# Teletupsud-Schematic.net
KiCad netlist of a schematic drawn in Altium Designer
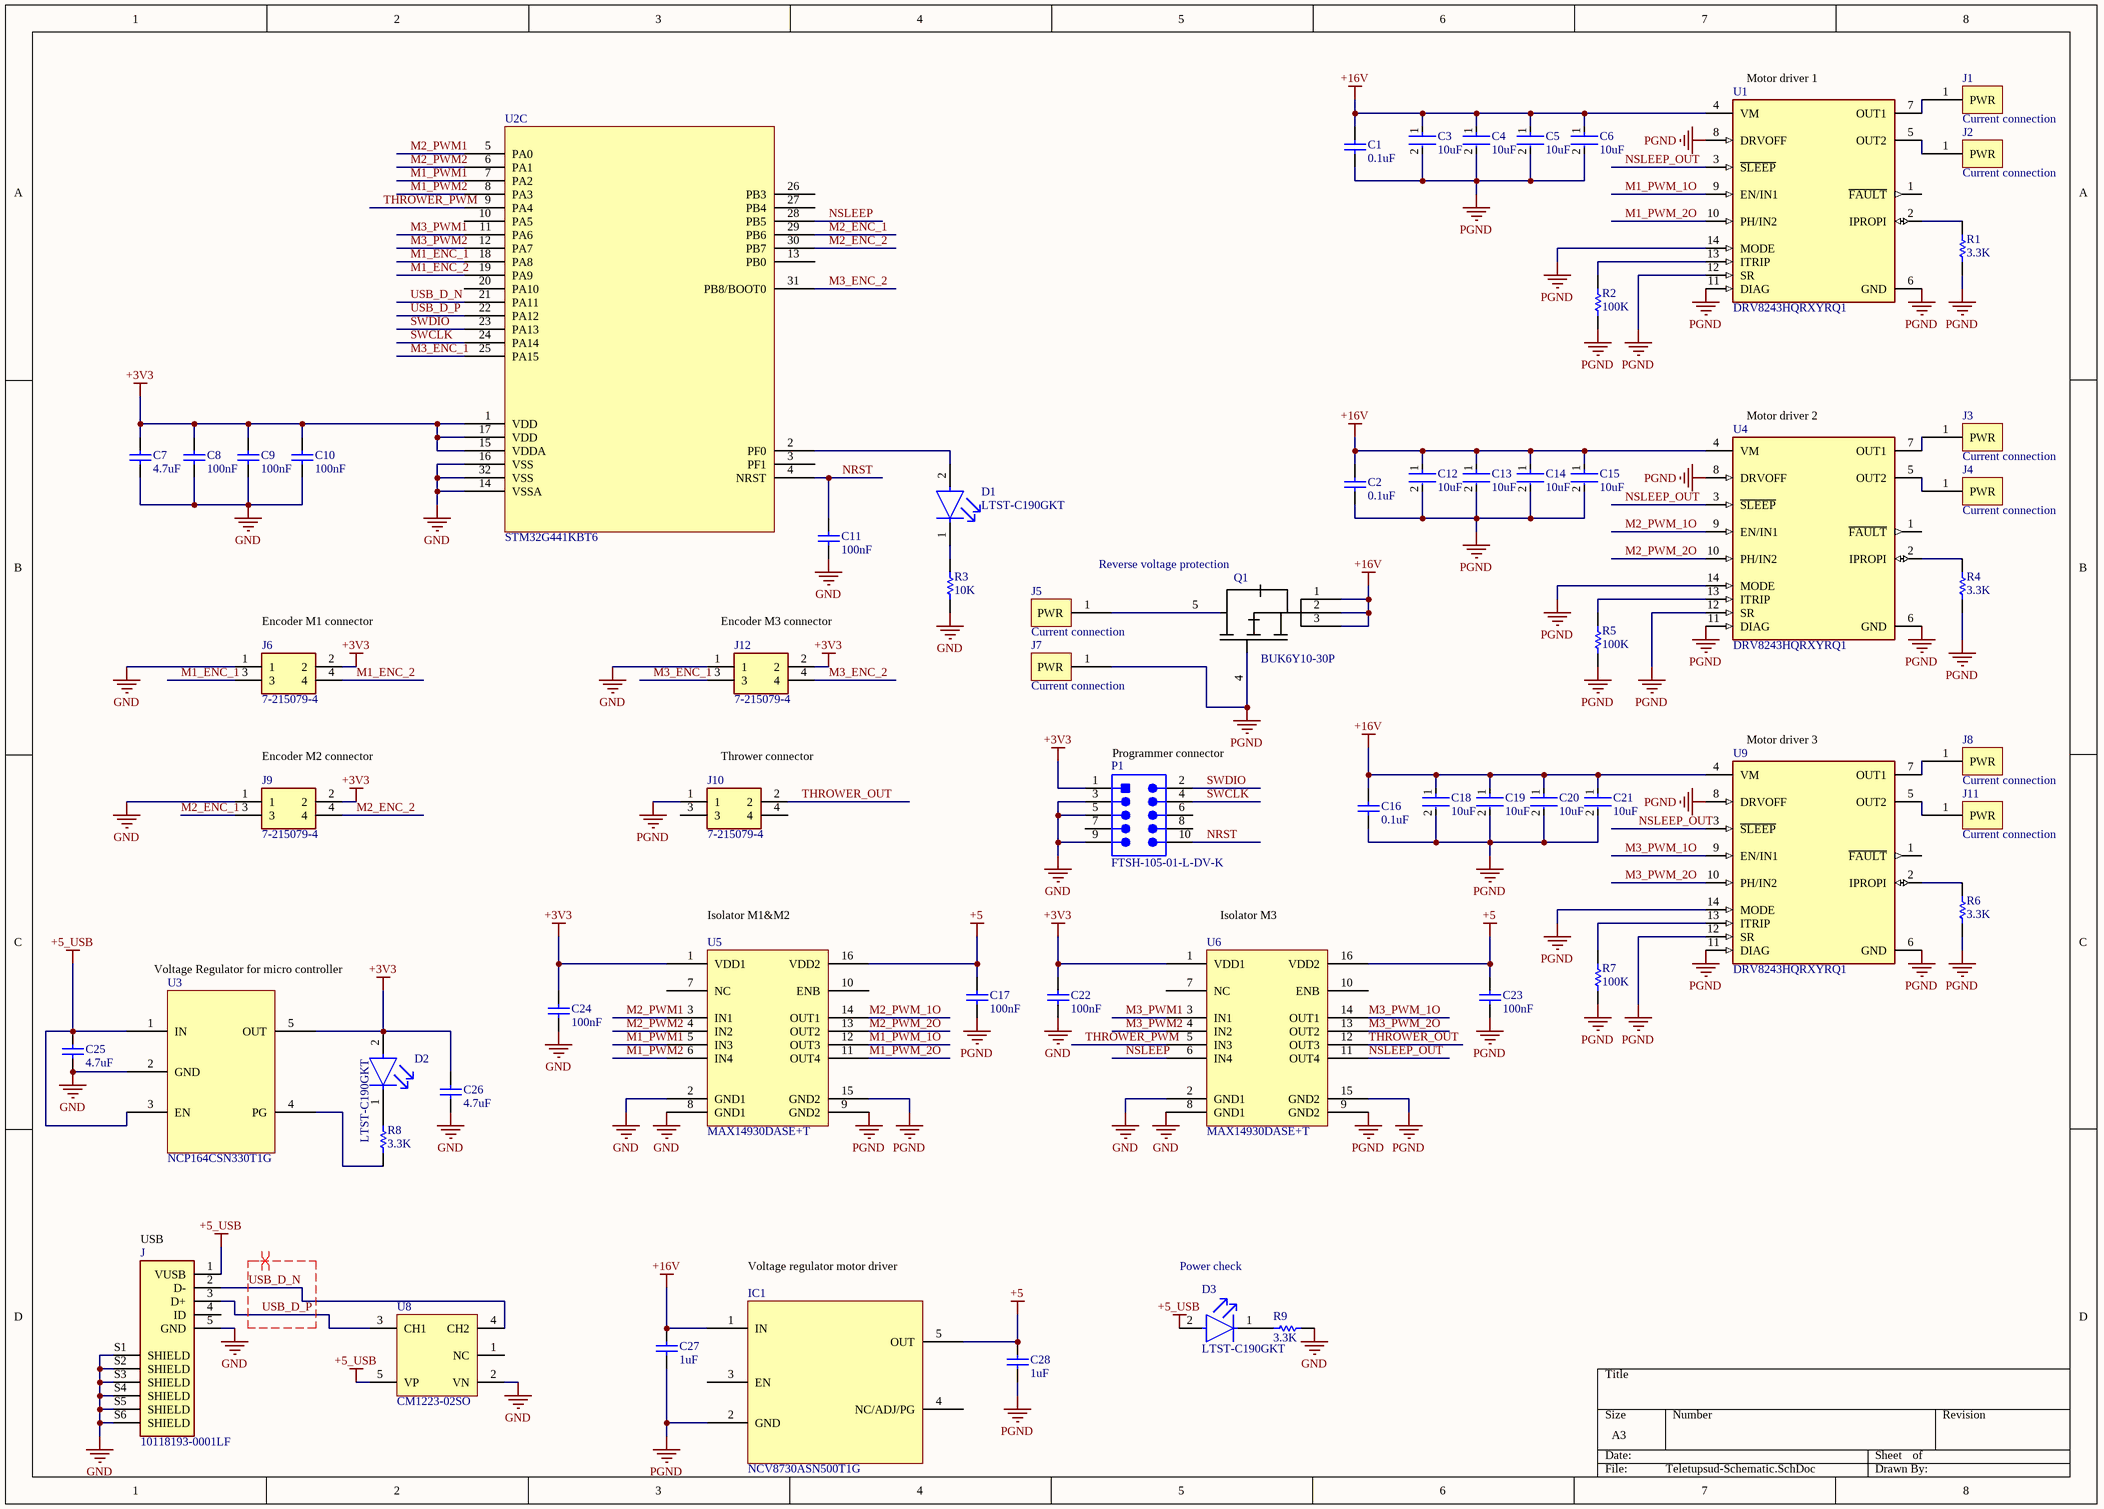
[diagram p0: Teletupsud-Schematic.SchDoc]

(export (version "E")
  (design (tool "Eeschema 10.0.6"))
  (components
    (comp (ref "C1")
      (value "0.1uF")
      (footprint "CAPC1608X90X35ML10T15")
      (description "Chip Capacitor, 22 pF, +/- 5%, 50 V, -55 to 125 degC, 0603 (1608 Metric), RoHS, Tape and Reel")
      (fields (field (name "MANUFACTURER") "Murata"))
      (libsource (lib "Altium Content Vault") (part "CAP-NP-2"))
    )
    (comp (ref "C2")
      (value "0.1uF")
      (footprint "CAPC1608X90X35ML10T15")
      (description "Chip Capacitor, 22 pF, +/- 5%, 50 V, -55 to 125 degC, 0603 (1608 Metric), RoHS, Tape and Reel")
      (fields (field (name "MANUFACTURER") "Murata"))
      (libsource (lib "Altium Content Vault") (part "CAP-NP-2"))
    )
    (comp (ref "C3")
      (value "10uF")
      (footprint "FP-GRM21B-0_15-IPC_A")
      (description "CAP CER 10UF 25V X5R 0805")
      (fields (field (name "VOLTAGE") "25V") (field (name "TOLERANCE") "10%"))
      (libsource (lib "Teletupsud") (part "b4654b650e69147ec39a6b967a45e02"))
    )
    (comp (ref "C4")
      (value "10uF")
      (footprint "FP-GRM21B-0_15-IPC_A")
      (description "CAP CER 10UF 25V X5R 0805")
      (fields (field (name "VOLTAGE") "25V") (field (name "TOLERANCE") "10%"))
      (libsource (lib "Teletupsud") (part "b4654b650e69147ec39a6b967a45e02"))
    )
    (comp (ref "C5")
      (value "10uF")
      (footprint "FP-GRM21B-0_15-IPC_A")
      (description "CAP CER 10UF 25V X5R 0805")
      (fields (field (name "VOLTAGE") "25V") (field (name "TOLERANCE") "10%"))
      (libsource (lib "Teletupsud") (part "b4654b650e69147ec39a6b967a45e02"))
    )
    (comp (ref "C6")
      (value "10uF")
      (footprint "FP-GRM21B-0_15-IPC_A")
      (description "CAP CER 10UF 25V X5R 0805")
      (fields (field (name "VOLTAGE") "25V") (field (name "TOLERANCE") "10%"))
      (libsource (lib "Teletupsud") (part "b4654b650e69147ec39a6b967a45e02"))
    )
    (comp (ref "C7")
      (value "4.7uF")
      (footprint "CAPC1608X90X35ML10T15")
      (description "Chip Capacitor, 22 pF, +/- 5%, 50 V, -55 to 125 degC, 0603 (1608 Metric), RoHS, Tape and Reel")
      (fields (field (name "MANUFACTURER") "Murata"))
      (libsource (lib "Altium Content Vault") (part "CAP-NP-2"))
    )
    (comp (ref "C8")
      (value "100nF")
      (footprint "CAPC1608X90X35ML10T15")
      (description "Chip Capacitor, 22 pF, +/- 5%, 50 V, -55 to 125 degC, 0603 (1608 Metric), RoHS, Tape and Reel")
      (fields (field (name "MANUFACTURER") "Murata"))
      (libsource (lib "Altium Content Vault") (part "CAP-NP-2"))
    )
    (comp (ref "C9")
      (value "100nF")
      (footprint "CAPC1608X90X35ML10T15")
      (description "Chip Capacitor, 22 pF, +/- 5%, 50 V, -55 to 125 degC, 0603 (1608 Metric), RoHS, Tape and Reel")
      (fields (field (name "MANUFACTURER") "Murata"))
      (libsource (lib "Altium Content Vault") (part "CAP-NP-2"))
    )
    (comp (ref "C10")
      (value "100nF")
      (footprint "CAPC1608X90X35ML10T15")
      (description "Chip Capacitor, 22 pF, +/- 5%, 50 V, -55 to 125 degC, 0603 (1608 Metric), RoHS, Tape and Reel")
      (fields (field (name "MANUFACTURER") "Murata"))
      (libsource (lib "Altium Content Vault") (part "CAP-NP-2"))
    )
    (comp (ref "C11")
      (value "100nF")
      (footprint "CAPC1608X90X35ML10T15")
      (description "Chip Capacitor, 22 pF, +/- 5%, 50 V, -55 to 125 degC, 0603 (1608 Metric), RoHS, Tape and Reel")
      (fields (field (name "MANUFACTURER") "Murata"))
      (libsource (lib "Altium Content Vault") (part "CAP-NP-2"))
    )
    (comp (ref "C12")
      (value "10uF")
      (footprint "FP-GRM21B-0_15-IPC_A")
      (description "CAP CER 10UF 25V X5R 0805")
      (fields (field (name "VOLTAGE") "25V") (field (name "TOLERANCE") "10%"))
      (libsource (lib "Teletupsud") (part "b4654b650e69147ec39a6b967a45e02"))
    )
    (comp (ref "C13")
      (value "10uF")
      (footprint "FP-GRM21B-0_15-IPC_A")
      (description "CAP CER 10UF 25V X5R 0805")
      (fields (field (name "VOLTAGE") "25V") (field (name "TOLERANCE") "10%"))
      (libsource (lib "Teletupsud") (part "b4654b650e69147ec39a6b967a45e02"))
    )
    (comp (ref "C14")
      (value "10uF")
      (footprint "FP-GRM21B-0_15-IPC_A")
      (description "CAP CER 10UF 25V X5R 0805")
      (fields (field (name "VOLTAGE") "25V") (field (name "TOLERANCE") "10%"))
      (libsource (lib "Teletupsud") (part "b4654b650e69147ec39a6b967a45e02"))
    )
    (comp (ref "C15")
      (value "10uF")
      (footprint "FP-GRM21B-0_15-IPC_A")
      (description "CAP CER 10UF 25V X5R 0805")
      (fields (field (name "VOLTAGE") "25V") (field (name "TOLERANCE") "10%"))
      (libsource (lib "Teletupsud") (part "b4654b650e69147ec39a6b967a45e02"))
    )
    (comp (ref "C16")
      (value "0.1uF")
      (footprint "CAPC1608X90X35ML10T15")
      (description "Chip Capacitor, 22 pF, +/- 5%, 50 V, -55 to 125 degC, 0603 (1608 Metric), RoHS, Tape and Reel")
      (fields (field (name "MANUFACTURER") "Murata"))
      (libsource (lib "Altium Content Vault") (part "CAP-NP-2"))
    )
    (comp (ref "C17")
      (value "100nF")
      (footprint "CAPC1608X90X35ML10T15")
      (description "Chip Capacitor, 22 pF, +/- 5%, 50 V, -55 to 125 degC, 0603 (1608 Metric), RoHS, Tape and Reel")
      (fields (field (name "MANUFACTURER") "Murata"))
      (libsource (lib "Altium Content Vault") (part "CAP-NP-2"))
    )
    (comp (ref "C18")
      (value "10uF")
      (footprint "FP-GRM21B-0_15-IPC_A")
      (description "CAP CER 10UF 25V X5R 0805")
      (fields (field (name "VOLTAGE") "25V") (field (name "TOLERANCE") "10%"))
      (libsource (lib "Teletupsud") (part "b4654b650e69147ec39a6b967a45e02"))
    )
    (comp (ref "C19")
      (value "10uF")
      (footprint "FP-GRM21B-0_15-IPC_A")
      (description "CAP CER 10UF 25V X5R 0805")
      (fields (field (name "VOLTAGE") "25V") (field (name "TOLERANCE") "10%"))
      (libsource (lib "Teletupsud") (part "b4654b650e69147ec39a6b967a45e02"))
    )
    (comp (ref "C20")
      (value "10uF")
      (footprint "FP-GRM21B-0_15-IPC_A")
      (description "CAP CER 10UF 25V X5R 0805")
      (fields (field (name "VOLTAGE") "25V") (field (name "TOLERANCE") "10%"))
      (libsource (lib "Teletupsud") (part "b4654b650e69147ec39a6b967a45e02"))
    )
    (comp (ref "C21")
      (value "10uF")
      (footprint "FP-GRM21B-0_15-IPC_A")
      (description "CAP CER 10UF 25V X5R 0805")
      (fields (field (name "VOLTAGE") "25V") (field (name "TOLERANCE") "10%"))
      (libsource (lib "Teletupsud") (part "b4654b650e69147ec39a6b967a45e02"))
    )
    (comp (ref "C22")
      (value "100nF")
      (footprint "CAPC1608X90X35ML10T15")
      (description "Chip Capacitor, 22 pF, +/- 5%, 50 V, -55 to 125 degC, 0603 (1608 Metric), RoHS, Tape and Reel")
      (fields (field (name "MANUFACTURER") "Murata"))
      (libsource (lib "Altium Content Vault") (part "CAP-NP-2"))
    )
    (comp (ref "C23")
      (value "100nF")
      (footprint "CAPC1608X90X35ML10T15")
      (description "Chip Capacitor, 22 pF, +/- 5%, 50 V, -55 to 125 degC, 0603 (1608 Metric), RoHS, Tape and Reel")
      (fields (field (name "MANUFACTURER") "Murata"))
      (libsource (lib "Altium Content Vault") (part "CAP-NP-2"))
    )
    (comp (ref "C24")
      (value "100nF")
      (footprint "CAPC1608X90X35ML10T15")
      (description "Chip Capacitor, 22 pF, +/- 5%, 50 V, -55 to 125 degC, 0603 (1608 Metric), RoHS, Tape and Reel")
      (fields (field (name "MANUFACTURER") "Murata"))
      (libsource (lib "Altium Content Vault") (part "CAP-NP-2"))
    )
    (comp (ref "C25")
      (value "4.7uF")
      (footprint "CAPC1608X90X35ML10T15")
      (description "Chip Capacitor, 22 pF, +/- 5%, 50 V, -55 to 125 degC, 0603 (1608 Metric), RoHS, Tape and Reel")
      (fields (field (name "MANUFACTURER") "Murata"))
      (libsource (lib "Altium Content Vault") (part "CAP-NP-2"))
    )
    (comp (ref "C26")
      (value "4.7uF")
      (footprint "CAPC1608X90X35ML10T15")
      (description "Chip Capacitor, 22 pF, +/- 5%, 50 V, -55 to 125 degC, 0603 (1608 Metric), RoHS, Tape and Reel")
      (fields (field (name "MANUFACTURER") "Murata"))
      (libsource (lib "Altium Content Vault") (part "CAP-NP-2"))
    )
    (comp (ref "C27")
      (value "1uF")
      (footprint "CAPC1608X90X35ML10T15")
      (description "Chip Capacitor, 22 pF, +/- 5%, 50 V, -55 to 125 degC, 0603 (1608 Metric), RoHS, Tape and Reel")
      (fields (field (name "MANUFACTURER") "Murata"))
      (libsource (lib "Altium Content Vault") (part "CAP-NP-2"))
    )
    (comp (ref "C28")
      (value "1uF")
      (footprint "CAPC1608X90X35ML10T15")
      (description "Chip Capacitor, 22 pF, +/- 5%, 50 V, -55 to 125 degC, 0603 (1608 Metric), RoHS, Tape and Reel")
      (fields (field (name "MANUFACTURER") "Murata"))
      (libsource (lib "Altium Content Vault") (part "CAP-NP-2"))
    )
    (comp (ref "D1")
      (value "LTST-C190GKT")
      (footprint "FP-LTST-C190GKT-MFG")
      (description "LED Uni-Color Green 565nm 2-Pin Chip LED T/R")
      (fields (field (name "VOLTAGE") "2V"))
      (libsource (lib "Teletupsud") (part "8706943c75ba83719d021d2fdc84c58"))
    )
    (comp (ref "D2")
      (value "LTST-C190GKT")
      (footprint "FP-LTST-C190GKT-MFG")
      (description "LED Uni-Color Green 565nm 2-Pin Chip LED T/R")
      (fields (field (name "VOLTAGE") "2V"))
      (libsource (lib "Teletupsud") (part "8706943c75ba83719d021d2fdc84c58"))
    )
    (comp (ref "D3")
      (value "LTST-C190GKT")
      (footprint "FP-LTST-C190GKT-MFG")
      (description "LED GREEN CLEAR CHIP SMD")
      (fields (field (name "VOLTAGE") "2V"))
      (libsource (lib "Altium Content Vault") (part "8706943c75ba83719d021d2fdc84c58"))
    )
    (comp (ref "IC1")
      (value "NCV8730ASN500T1G")
      (footprint "SOP95P275X110-5N")
      (libsource (lib "") (part "New symbol 1_3"))
    )
    (comp (ref "J")
      (value "10118193-0001LF")
      (footprint "FCI_10118193-0001LF")
      (description "USB - micro B USB 2.0 Receptacle Connector 5 Position Surface Mount, Right Angle; Through Hole")
      (fields (field (name "MF") "Amphenol ICC"))
      (libsource (lib "Teletupsud") (part "10118193-0001LF"))
    )
    (comp (ref "J1")
      (value "Current connection")
      (footprint "New footprint 1")
      (libsource (lib "Teletupsud") (part "New symbol 1"))
    )
    (comp (ref "J2")
      (value "Current connection")
      (footprint "New footprint 1")
      (libsource (lib "Teletupsud") (part "New symbol 1"))
    )
    (comp (ref "J3")
      (value "Current connection")
      (footprint "New footprint 1")
      (libsource (lib "Teletupsud") (part "New symbol 1"))
    )
    (comp (ref "J4")
      (value "Current connection")
      (footprint "New footprint 1")
      (libsource (lib "Teletupsud") (part "New symbol 1"))
    )
    (comp (ref "J5")
      (value "Current connection")
      (footprint "New footprint 1")
      (libsource (lib "") (part "New symbol 1_2"))
    )
    (comp (ref "J6")
      (value "7-215079-4")
      (footprint "TE_7-215079-4")
      (description "Micro-MaTch 4 Position 1.27 mm Pitch Vertical Female-on-Board Connector")
      (fields (field (name "MF") "TE Connectivity"))
      (libsource (lib "Teletupsud") (part "7-215079-4"))
    )
    (comp (ref "J7")
      (value "Current connection")
      (footprint "New footprint 1")
      (libsource (lib "") (part "New symbol 1_2"))
    )
    (comp (ref "J8")
      (value "Current connection")
      (footprint "New footprint 1")
      (libsource (lib "Teletupsud") (part "New symbol 1"))
    )
    (comp (ref "J9")
      (value "7-215079-4")
      (footprint "TE_7-215079-4")
      (description "Micro-MaTch 4 Position 1.27 mm Pitch Vertical Female-on-Board Connector")
      (fields (field (name "MF") "TE Connectivity"))
      (libsource (lib "Teletupsud") (part "7-215079-4"))
    )
    (comp (ref "J10")
      (value "7-215079-4")
      (footprint "TE_7-215079-4")
      (description "Micro-MaTch 4 Position 1.27 mm Pitch Vertical Female-on-Board Connector")
      (fields (field (name "MF") "TE Connectivity"))
      (libsource (lib "Teletupsud") (part "7-215079-4"))
    )
    (comp (ref "J11")
      (value "Current connection")
      (footprint "New footprint 1")
      (libsource (lib "Teletupsud") (part "New symbol 1"))
    )
    (comp (ref "J12")
      (value "7-215079-4")
      (footprint "TE_7-215079-4")
      (description "Micro-MaTch 4 Position 1.27 mm Pitch Vertical Female-on-Board Connector")
      (fields (field (name "MF") "TE Connectivity"))
      (libsource (lib "Teletupsud") (part "7-215079-4"))
    )
    (comp (ref "P1")
      (value "FTSH-105-01-L-DV-K")
      (footprint "SMTC-FTSH-105-01-L-DV-K_V")
      (description "Male Header, Pitch 1.27 mm, 2 x 5 Position, Height 6.25 mm")
      (fields (field (name "MANUFACTURER") "Samtec"))
      (libsource (lib "Altium Content Vault") (part "CN-2P-M-R10"))
    )
    (comp (ref "Q1")
      (value "BUK6Y10-30P")
      (footprint "TO127P600X120-5N")
      (libsource (lib "") (part "New symbol 1_1"))
    )
    (comp (ref "R1")
      (value "3.3K")
      (footprint "RESC1609X50X30NL8T20")
      (description "Chip Resistor, 0 Ohm, Jumper, 100 mW, -55 to 155 degC, 0603 (1608 Metric), RoHS, Tape and Reel")
      (fields (field (name "MANUFACTURER") "Vishay Semiconductor"))
      (libsource (lib "Altium Content Vault") (part "RES-2"))
    )
    (comp (ref "R2")
      (value "100K")
      (footprint "RESC1609X50X30NL8T20")
      (description "Chip Resistor, 0 Ohm, Jumper, 100 mW, -55 to 155 degC, 0603 (1608 Metric), RoHS, Tape and Reel")
      (fields (field (name "MANUFACTURER") "Vishay Semiconductor"))
      (libsource (lib "Altium Content Vault") (part "RES-2"))
    )
    (comp (ref "R3")
      (value "10K")
      (footprint "RESC1609X50X30NL8T20")
      (description "Chip Resistor, 0 Ohm, Jumper, 100 mW, -55 to 155 degC, 0603 (1608 Metric), RoHS, Tape and Reel")
      (fields (field (name "MANUFACTURER") "Vishay Semiconductor"))
      (libsource (lib "Altium Content Vault") (part "RES-2"))
    )
    (comp (ref "R4")
      (value "3.3K")
      (footprint "RESC1609X50X30NL8T20")
      (description "Chip Resistor, 0 Ohm, Jumper, 100 mW, -55 to 155 degC, 0603 (1608 Metric), RoHS, Tape and Reel")
      (fields (field (name "MANUFACTURER") "Vishay Semiconductor"))
      (libsource (lib "Altium Content Vault") (part "RES-2"))
    )
    (comp (ref "R5")
      (value "100K")
      (footprint "RESC1609X50X30NL8T20")
      (description "Chip Resistor, 0 Ohm, Jumper, 100 mW, -55 to 155 degC, 0603 (1608 Metric), RoHS, Tape and Reel")
      (fields (field (name "MANUFACTURER") "Vishay Semiconductor"))
      (libsource (lib "Altium Content Vault") (part "RES-2"))
    )
    (comp (ref "R6")
      (value "3.3K")
      (footprint "RESC1609X50X30NL8T20")
      (description "Chip Resistor, 0 Ohm, Jumper, 100 mW, -55 to 155 degC, 0603 (1608 Metric), RoHS, Tape and Reel")
      (fields (field (name "MANUFACTURER") "Vishay Semiconductor"))
      (libsource (lib "Altium Content Vault") (part "RES-2"))
    )
    (comp (ref "R7")
      (value "100K")
      (footprint "RESC1609X50X30NL8T20")
      (description "Chip Resistor, 0 Ohm, Jumper, 100 mW, -55 to 155 degC, 0603 (1608 Metric), RoHS, Tape and Reel")
      (fields (field (name "MANUFACTURER") "Vishay Semiconductor"))
      (libsource (lib "Altium Content Vault") (part "RES-2"))
    )
    (comp (ref "R8")
      (value "3.3K")
      (footprint "RESC1609X50X30NL8T20")
      (description "Chip Resistor, 0 Ohm, Jumper, 100 mW, -55 to 155 degC, 0603 (1608 Metric), RoHS, Tape and Reel")
      (fields (field (name "MANUFACTURER") "Vishay Semiconductor"))
      (libsource (lib "Altium Content Vault") (part "RES-2"))
    )
    (comp (ref "R9")
      (value "3.3K")
      (footprint "RESC1609X50X30NL8T20")
      (description "Chip Resistor, 0 Ohm, Jumper, 100 mW, -55 to 155 degC, 0603 (1608 Metric), RoHS, Tape and Reel")
      (fields (field (name "MANUFACTURER") "Vishay Semiconductor"))
      (libsource (lib "Altium Content Vault") (part "RES-2"))
    )
    (comp (ref "U1")
      (value "DRV8243HQRXYRQ1")
      (footprint "FP-RXY0014A-MFG")
      (libsource (lib "Teletupsud") (part "e63e13eb07ecfdbca845f52d5221c39"))
    )
    (comp (ref "U2")
      (value "STM32G441KBT6")
      (footprint "QFP32_STM32")
      (libsource (lib "Teletupsud") (part "STM32G441KBT6"))
    )
    (comp (ref "U3")
      (value "NCP164CSN330T1G")
      (footprint "SOP95P275X110-5N")
      (libsource (lib "Teletupsud") (part "NCP164CSN330T1G-Symbol-1"))
    )
    (comp (ref "U4")
      (value "DRV8243HQRXYRQ1")
      (footprint "FP-RXY0014A-MFG")
      (libsource (lib "Teletupsud") (part "e63e13eb07ecfdbca845f52d5221c39"))
    )
    (comp (ref "U5")
      (value "MAX14930DASE+T")
      (footprint "SOIC127P600X175-16N")
      (description "Digital Isolator, 4Ch, -40 To 125Deg C Rohs Compliant: Yes")
      (libsource (lib "Teletupsud") (part "MAX14930DASE+T-Symbol-1"))
    )
    (comp (ref "U6")
      (value "MAX14930DASE+T")
      (footprint "SOIC127P600X175-16N")
      (description "Digital Isolator, 4Ch, -40 To 125Deg C Rohs Compliant: Yes")
      (libsource (lib "Teletupsud") (part "MAX14930DASE+T-Symbol-1"))
    )
    (comp (ref "U8")
      (value "CM1223-02SO")
      (footprint "ONSC-SOT23-5-527AH-01_L")
      (fields (field (name "MANUFACTURER") "On Semiconductor"))
      (libsource (lib "Altium Content Vault") (part "ONSC-CM1223-SOT-23-5-527AH-01"))
    )
    (comp (ref "U9")
      (value "DRV8243HQRXYRQ1")
      (footprint "FP-RXY0014A-MFG")
      (libsource (lib "Teletupsud") (part "e63e13eb07ecfdbca845f52d5221c39"))
    )
  )
  (nets
    (net (code "1") (name "+3V3") (class "Default")
      (node (ref "C10") (pin "2") (pinfunction "2_2") (pintype "passive"))
      (node (ref "C22") (pin "2") (pinfunction "2_2") (pintype "passive"))
      (node (ref "C24") (pin "2") (pinfunction "2_2") (pintype "passive"))
      (node (ref "C26") (pin "2") (pinfunction "2_2") (pintype "passive"))
      (node (ref "C7") (pin "2") (pinfunction "2_2") (pintype "passive"))
      (node (ref "C8") (pin "2") (pinfunction "2_2") (pintype "passive"))
      (node (ref "C9") (pin "2") (pinfunction "2_2") (pintype "passive"))
      (node (ref "D2") (pin "2") (pinfunction "A_2") (pintype "passive"))
      (node (ref "J12") (pin "2") (pinfunction "2_2") (pintype "passive"))
      (node (ref "J6") (pin "2") (pinfunction "2_2") (pintype "passive"))
      (node (ref "J9") (pin "2") (pinfunction "2_2") (pintype "passive"))
      (node (ref "P1") (pin "1") (pinfunction "1_1") (pintype "passive"))
      (node (ref "U2") (pin "1") (pinfunction "VDD_1") (pintype "passive"))
      (node (ref "U2") (pin "15") (pinfunction "VDDA_15") (pintype "passive"))
      (node (ref "U2") (pin "17") (pinfunction "VDD_17") (pintype "passive"))
      (node (ref "U3") (pin "5") (pinfunction "OUT_5") (pintype "passive"))
      (node (ref "U5") (pin "1") (pinfunction "VDD1_1") (pintype "passive"))
      (node (ref "U6") (pin "1") (pinfunction "VDD1_1") (pintype "passive"))
    )
    (net (code "2") (name "+5") (class "Default")
      (node (ref "C17") (pin "2") (pinfunction "2_2") (pintype "passive"))
      (node (ref "C23") (pin "2") (pinfunction "2_2") (pintype "passive"))
      (node (ref "C28") (pin "2") (pinfunction "2_2") (pintype "passive"))
      (node (ref "IC1") (pin "5") (pinfunction "OUT_5") (pintype "passive"))
      (node (ref "U5") (pin "16") (pinfunction "VDD2_16") (pintype "passive"))
      (node (ref "U6") (pin "16") (pinfunction "VDD2_16") (pintype "passive"))
    )
    (net (code "3") (name "+5_USB") (class "Default")
      (node (ref "C25") (pin "2") (pinfunction "2_2") (pintype "passive"))
      (node (ref "D3") (pin "2") (pinfunction "A_2") (pintype "passive"))
      (node (ref "J") (pin "1") (pinfunction "VUSB_1") (pintype "passive"))
      (node (ref "U3") (pin "1") (pinfunction "IN_1") (pintype "passive"))
      (node (ref "U3") (pin "3") (pinfunction "EN_3") (pintype "passive"))
      (node (ref "U8") (pin "5") (pinfunction "VP_5") (pintype "power_in"))
    )
    (net (code "4") (name "+16V") (class "Default")
      (node (ref "C1") (pin "2") (pinfunction "2_2") (pintype "passive"))
      (node (ref "C12") (pin "1") (pinfunction "1_1") (pintype "passive"))
      (node (ref "C13") (pin "1") (pinfunction "1_1") (pintype "passive"))
      (node (ref "C14") (pin "1") (pinfunction "1_1") (pintype "passive"))
      (node (ref "C15") (pin "1") (pinfunction "1_1") (pintype "passive"))
      (node (ref "C16") (pin "2") (pinfunction "2_2") (pintype "passive"))
      (node (ref "C18") (pin "1") (pinfunction "1_1") (pintype "passive"))
      (node (ref "C19") (pin "1") (pinfunction "1_1") (pintype "passive"))
      (node (ref "C2") (pin "2") (pinfunction "2_2") (pintype "passive"))
      (node (ref "C20") (pin "1") (pinfunction "1_1") (pintype "passive"))
      (node (ref "C21") (pin "1") (pinfunction "1_1") (pintype "passive"))
      (node (ref "C27") (pin "2") (pinfunction "2_2") (pintype "passive"))
      (node (ref "C3") (pin "1") (pinfunction "1_1") (pintype "passive"))
      (node (ref "C4") (pin "1") (pinfunction "1_1") (pintype "passive"))
      (node (ref "C5") (pin "1") (pinfunction "1_1") (pintype "passive"))
      (node (ref "C6") (pin "1") (pinfunction "1_1") (pintype "passive"))
      (node (ref "IC1") (pin "1") (pinfunction "IN_1") (pintype "passive"))
      (node (ref "Q1") (pin "1") (pintype "passive"))
      (node (ref "Q1") (pin "2") (pintype "passive"))
      (node (ref "Q1") (pin "3") (pintype "passive"))
      (node (ref "U1") (pin "4") (pinfunction "VM_4") (pintype "power_in"))
      (node (ref "U4") (pin "4") (pinfunction "VM_4") (pintype "power_in"))
      (node (ref "U9") (pin "4") (pinfunction "VM_4") (pintype "power_in"))
    )
    (net (code "5") (name "/M1_ENC_1") (class "Default")
      (node (ref "J6") (pin "3") (pinfunction "3_3") (pintype "passive"))
      (node (ref "U2") (pin "18") (pinfunction "PA8_18") (pintype "passive"))
    )
    (net (code "6") (name "/M1_ENC_2") (class "Default")
      (node (ref "J6") (pin "4") (pinfunction "4_4") (pintype "passive"))
      (node (ref "U2") (pin "19") (pinfunction "PA9_19") (pintype "passive"))
    )
    (net (code "7") (name "/M1_PWM1") (class "Default")
      (node (ref "U2") (pin "7") (pinfunction "PA2_7") (pintype "passive"))
      (node (ref "U5") (pin "5") (pinfunction "IN3_5") (pintype "passive"))
    )
    (net (code "8") (name "/M1_PWM2") (class "Default")
      (node (ref "U2") (pin "8") (pinfunction "PA3_8") (pintype "passive"))
      (node (ref "U5") (pin "6") (pinfunction "IN4_6") (pintype "passive"))
    )
    (net (code "9") (name "/M1_PWM_1O") (class "Default")
      (node (ref "U1") (pin "9") (pinfunction "EN/IN1_9") (pintype "input"))
      (node (ref "U5") (pin "12") (pinfunction "OUT3_12") (pintype "passive"))
    )
    (net (code "10") (name "/M1_PWM_2O") (class "Default")
      (node (ref "U1") (pin "10") (pinfunction "PH/IN2_10") (pintype "input"))
      (node (ref "U5") (pin "11") (pinfunction "OUT4_11") (pintype "passive"))
    )
    (net (code "11") (name "/M2_ENC_1") (class "Default")
      (node (ref "J9") (pin "3") (pinfunction "3_3") (pintype "passive"))
      (node (ref "U2") (pin "29") (pinfunction "PB6_29") (pintype "passive"))
    )
    (net (code "12") (name "/M2_ENC_2") (class "Default")
      (node (ref "J9") (pin "4") (pinfunction "4_4") (pintype "passive"))
      (node (ref "U2") (pin "30") (pinfunction "PB7_30") (pintype "passive"))
    )
    (net (code "13") (name "/M2_PWM1") (class "Default")
      (node (ref "U2") (pin "5") (pinfunction "PA0_5") (pintype "passive"))
      (node (ref "U5") (pin "3") (pinfunction "IN1_3") (pintype "passive"))
    )
    (net (code "14") (name "/M2_PWM2") (class "Default")
      (node (ref "U2") (pin "6") (pinfunction "PA1_6") (pintype "passive"))
      (node (ref "U5") (pin "4") (pinfunction "IN2_4") (pintype "passive"))
    )
    (net (code "15") (name "/M2_PWM_1O") (class "Default")
      (node (ref "U4") (pin "9") (pinfunction "EN/IN1_9") (pintype "input"))
      (node (ref "U5") (pin "14") (pinfunction "OUT1_14") (pintype "passive"))
    )
    (net (code "16") (name "/M2_PWM_2O") (class "Default")
      (node (ref "U4") (pin "10") (pinfunction "PH/IN2_10") (pintype "input"))
      (node (ref "U5") (pin "13") (pinfunction "OUT2_13") (pintype "passive"))
    )
    (net (code "17") (name "/M3_ENC_1") (class "Default")
      (node (ref "J12") (pin "3") (pinfunction "3_3") (pintype "passive"))
      (node (ref "U2") (pin "25") (pinfunction "PA15_25") (pintype "passive"))
    )
    (net (code "18") (name "/M3_ENC_2") (class "Default")
      (node (ref "J12") (pin "4") (pinfunction "4_4") (pintype "passive"))
      (node (ref "U2") (pin "31") (pinfunction "PB8/BOOT0_31") (pintype "passive"))
    )
    (net (code "19") (name "/M3_PWM1") (class "Default")
      (node (ref "U2") (pin "11") (pinfunction "PA6_11") (pintype "passive"))
      (node (ref "U6") (pin "3") (pinfunction "IN1_3") (pintype "passive"))
    )
    (net (code "20") (name "/M3_PWM2") (class "Default")
      (node (ref "U2") (pin "12") (pinfunction "PA7_12") (pintype "passive"))
      (node (ref "U6") (pin "4") (pinfunction "IN2_4") (pintype "passive"))
    )
    (net (code "21") (name "/M3_PWM_1O") (class "Default")
      (node (ref "U6") (pin "14") (pinfunction "OUT1_14") (pintype "passive"))
      (node (ref "U9") (pin "9") (pinfunction "EN/IN1_9") (pintype "input"))
    )
    (net (code "22") (name "/M3_PWM_2O") (class "Default")
      (node (ref "U6") (pin "13") (pinfunction "OUT2_13") (pintype "passive"))
      (node (ref "U9") (pin "10") (pinfunction "PH/IN2_10") (pintype "input"))
    )
    (net (code "23") (name "/NRST") (class "Default")
      (node (ref "C11") (pin "2") (pinfunction "2_2") (pintype "passive"))
      (node (ref "P1") (pin "10") (pinfunction "10_10") (pintype "passive"))
      (node (ref "U2") (pin "4") (pinfunction "NRST_4") (pintype "passive"))
    )
    (net (code "24") (name "/NSLEEP") (class "Default")
      (node (ref "U2") (pin "28") (pinfunction "PB5_28") (pintype "passive"))
      (node (ref "U6") (pin "6") (pinfunction "IN4_6") (pintype "passive"))
    )
    (net (code "25") (name "/NSLEEP_OUT") (class "Default")
      (node (ref "U1") (pin "3") (pinfunction "~{SLEEP}_3") (pintype "input"))
      (node (ref "U4") (pin "3") (pinfunction "~{SLEEP}_3") (pintype "input"))
      (node (ref "U6") (pin "11") (pinfunction "OUT4_11") (pintype "passive"))
      (node (ref "U9") (pin "3") (pinfunction "~{SLEEP}_3") (pintype "input"))
    )
    (net (code "26") (name "/SWCLK") (class "Default")
      (node (ref "P1") (pin "4") (pinfunction "4_4") (pintype "passive"))
      (node (ref "U2") (pin "24") (pinfunction "PA14_24") (pintype "passive"))
    )
    (net (code "27") (name "/SWDIO") (class "Default")
      (node (ref "P1") (pin "2") (pinfunction "2_2") (pintype "passive"))
      (node (ref "U2") (pin "23") (pinfunction "PA13_23") (pintype "passive"))
    )
    (net (code "28") (name "/THROWER_OUT") (class "Default")
      (node (ref "J10") (pin "2") (pinfunction "2_2") (pintype "passive"))
      (node (ref "U6") (pin "12") (pinfunction "OUT3_12") (pintype "passive"))
    )
    (net (code "29") (name "/THROWER_PWM") (class "Default")
      (node (ref "U2") (pin "9") (pinfunction "PA4_9") (pintype "passive"))
      (node (ref "U6") (pin "5") (pinfunction "IN3_5") (pintype "passive"))
    )
    (net (code "30") (name "/USB_D_N") (class "Default")
      (node (ref "J") (pin "2") (pinfunction "D-_2") (pintype "passive"))
      (node (ref "U2") (pin "21") (pinfunction "PA11_21") (pintype "passive"))
      (node (ref "U8") (pin "4") (pinfunction "CH2_4") (pintype "passive"))
    )
    (net (code "31") (name "/USB_D_P") (class "Default")
      (node (ref "J") (pin "3") (pinfunction "D+_3") (pintype "passive"))
      (node (ref "U2") (pin "22") (pinfunction "PA12_22") (pintype "passive"))
      (node (ref "U8") (pin "3") (pinfunction "CH1_3") (pintype "passive"))
    )
    (net (code "32") (name "GND") (class "Default")
      (node (ref "C10") (pin "1") (pinfunction "1_1") (pintype "passive"))
      (node (ref "C11") (pin "1") (pinfunction "1_1") (pintype "passive"))
      (node (ref "C22") (pin "1") (pinfunction "1_1") (pintype "passive"))
      (node (ref "C24") (pin "1") (pinfunction "1_1") (pintype "passive"))
      (node (ref "C25") (pin "1") (pinfunction "1_1") (pintype "passive"))
      (node (ref "C26") (pin "1") (pinfunction "1_1") (pintype "passive"))
      (node (ref "C7") (pin "1") (pinfunction "1_1") (pintype "passive"))
      (node (ref "C8") (pin "1") (pinfunction "1_1") (pintype "passive"))
      (node (ref "C9") (pin "1") (pinfunction "1_1") (pintype "passive"))
      (node (ref "J") (pin "5") (pinfunction "GND_5") (pintype "passive"))
      (node (ref "J") (pin "S1") (pinfunction "SHIELD_S1") (pintype "passive"))
      (node (ref "J") (pin "S2") (pinfunction "SHIELD_S2") (pintype "passive"))
      (node (ref "J") (pin "S3") (pinfunction "SHIELD_S3") (pintype "passive"))
      (node (ref "J") (pin "S4") (pinfunction "SHIELD_S4") (pintype "passive"))
      (node (ref "J") (pin "S5") (pinfunction "SHIELD_S5") (pintype "passive"))
      (node (ref "J") (pin "S6") (pinfunction "SHIELD_S6") (pintype "passive"))
      (node (ref "J12") (pin "1") (pinfunction "1_1") (pintype "passive"))
      (node (ref "J6") (pin "1") (pinfunction "1_1") (pintype "passive"))
      (node (ref "J9") (pin "1") (pinfunction "1_1") (pintype "passive"))
      (node (ref "P1") (pin "3") (pinfunction "3_3") (pintype "passive"))
      (node (ref "P1") (pin "5") (pinfunction "5_5") (pintype "passive"))
      (node (ref "P1") (pin "9") (pinfunction "9_9") (pintype "passive"))
      (node (ref "R3") (pin "1") (pinfunction "1_1") (pintype "passive"))
      (node (ref "R9") (pin "2") (pinfunction "2_2") (pintype "passive"))
      (node (ref "U2") (pin "14") (pinfunction "VSSA_14") (pintype "passive"))
      (node (ref "U2") (pin "16") (pinfunction "VSS_16") (pintype "passive"))
      (node (ref "U2") (pin "32") (pinfunction "VSS_32") (pintype "passive"))
      (node (ref "U3") (pin "2") (pinfunction "GND_2") (pintype "passive"))
      (node (ref "U5") (pin "2") (pinfunction "GND1_2") (pintype "passive"))
      (node (ref "U5") (pin "8") (pinfunction "GND1_8") (pintype "passive"))
      (node (ref "U6") (pin "2") (pinfunction "GND1_2") (pintype "passive"))
      (node (ref "U6") (pin "8") (pinfunction "GND1_8") (pintype "passive"))
      (node (ref "U8") (pin "2") (pinfunction "VN_2") (pintype "power_in"))
    )
    (net (code "33") (name "Net-(D1-A)") (class "Default")
      (node (ref "D1") (pin "2") (pinfunction "A_2") (pintype "passive"))
      (node (ref "U2") (pin "2") (pinfunction "PF0_2") (pintype "passive"))
    )
    (net (code "34") (name "Net-(D1-C)") (class "Default")
      (node (ref "D1") (pin "1") (pinfunction "C_1") (pintype "passive"))
      (node (ref "R3") (pin "2") (pinfunction "2_2") (pintype "passive"))
    )
    (net (code "35") (name "Net-(D2-C)") (class "Default")
      (node (ref "D2") (pin "1") (pinfunction "C_1") (pintype "passive"))
      (node (ref "R8") (pin "2") (pinfunction "2_2") (pintype "passive"))
    )
    (net (code "36") (name "Net-(D3-C)") (class "Default")
      (node (ref "D3") (pin "1") (pinfunction "C_1") (pintype "passive"))
      (node (ref "R9") (pin "1") (pinfunction "1_1") (pintype "passive"))
    )
    (net (code "37") (name "Net-(J1-PWR)") (class "Default")
      (node (ref "J1") (pin "1") (pinfunction "PWR_1") (pintype "passive"))
      (node (ref "U1") (pin "7") (pinfunction "OUT1_7") (pintype "passive"))
    )
    (net (code "38") (name "Net-(J2-PWR)") (class "Default")
      (node (ref "J2") (pin "1") (pinfunction "PWR_1") (pintype "passive"))
      (node (ref "U1") (pin "5") (pinfunction "OUT2_5") (pintype "passive"))
    )
    (net (code "39") (name "Net-(J3-PWR)") (class "Default")
      (node (ref "J3") (pin "1") (pinfunction "PWR_1") (pintype "passive"))
      (node (ref "U4") (pin "7") (pinfunction "OUT1_7") (pintype "passive"))
    )
    (net (code "40") (name "Net-(J4-PWR)") (class "Default")
      (node (ref "J4") (pin "1") (pinfunction "PWR_1") (pintype "passive"))
      (node (ref "U4") (pin "5") (pinfunction "OUT2_5") (pintype "passive"))
    )
    (net (code "41") (name "Net-(J5-PWR)") (class "Default")
      (node (ref "J5") (pin "1") (pinfunction "PWR_1") (pintype "passive"))
      (node (ref "Q1") (pin "5") (pintype "passive"))
    )
    (net (code "42") (name "Net-(J8-PWR)") (class "Default")
      (node (ref "J8") (pin "1") (pinfunction "PWR_1") (pintype "passive"))
      (node (ref "U9") (pin "7") (pinfunction "OUT1_7") (pintype "passive"))
    )
    (net (code "43") (name "Net-(J11-PWR)") (class "Default")
      (node (ref "J11") (pin "1") (pinfunction "PWR_1") (pintype "passive"))
      (node (ref "U9") (pin "5") (pinfunction "OUT2_5") (pintype "passive"))
    )
    (net (code "44") (name "Net-(U1-IPROPI)") (class "Default")
      (node (ref "R1") (pin "2") (pinfunction "2_2") (pintype "passive"))
      (node (ref "U1") (pin "2") (pinfunction "IPROPI_2") (pintype "bidirectional"))
    )
    (net (code "45") (name "Net-(U1-ITRIP)") (class "Default")
      (node (ref "R2") (pin "2") (pinfunction "2_2") (pintype "passive"))
      (node (ref "U1") (pin "13") (pinfunction "ITRIP_13") (pintype "input"))
    )
    (net (code "46") (name "Net-(U3-PG)") (class "Default")
      (node (ref "R8") (pin "1") (pinfunction "1_1") (pintype "passive"))
      (node (ref "U3") (pin "4") (pinfunction "PG_4") (pintype "passive"))
    )
    (net (code "47") (name "Net-(U4-IPROPI)") (class "Default")
      (node (ref "R4") (pin "2") (pinfunction "2_2") (pintype "passive"))
      (node (ref "U4") (pin "2") (pinfunction "IPROPI_2") (pintype "bidirectional"))
    )
    (net (code "48") (name "Net-(U4-ITRIP)") (class "Default")
      (node (ref "R5") (pin "2") (pinfunction "2_2") (pintype "passive"))
      (node (ref "U4") (pin "13") (pinfunction "ITRIP_13") (pintype "input"))
    )
    (net (code "49") (name "Net-(U9-IPROPI)") (class "Default")
      (node (ref "R6") (pin "2") (pinfunction "2_2") (pintype "passive"))
      (node (ref "U9") (pin "2") (pinfunction "IPROPI_2") (pintype "bidirectional"))
    )
    (net (code "50") (name "Net-(U9-ITRIP)") (class "Default")
      (node (ref "R7") (pin "2") (pinfunction "2_2") (pintype "passive"))
      (node (ref "U9") (pin "13") (pinfunction "ITRIP_13") (pintype "input"))
    )
    (net (code "51") (name "PGND") (class "Default")
      (node (ref "C1") (pin "1") (pinfunction "1_1") (pintype "passive"))
      (node (ref "C12") (pin "2") (pinfunction "2_2") (pintype "passive"))
      (node (ref "C13") (pin "2") (pinfunction "2_2") (pintype "passive"))
      (node (ref "C14") (pin "2") (pinfunction "2_2") (pintype "passive"))
      (node (ref "C15") (pin "2") (pinfunction "2_2") (pintype "passive"))
      (node (ref "C16") (pin "1") (pinfunction "1_1") (pintype "passive"))
      (node (ref "C17") (pin "1") (pinfunction "1_1") (pintype "passive"))
      (node (ref "C18") (pin "2") (pinfunction "2_2") (pintype "passive"))
      (node (ref "C19") (pin "2") (pinfunction "2_2") (pintype "passive"))
      (node (ref "C2") (pin "1") (pinfunction "1_1") (pintype "passive"))
      (node (ref "C20") (pin "2") (pinfunction "2_2") (pintype "passive"))
      (node (ref "C21") (pin "2") (pinfunction "2_2") (pintype "passive"))
      (node (ref "C23") (pin "1") (pinfunction "1_1") (pintype "passive"))
      (node (ref "C27") (pin "1") (pinfunction "1_1") (pintype "passive"))
      (node (ref "C28") (pin "1") (pinfunction "1_1") (pintype "passive"))
      (node (ref "C3") (pin "2") (pinfunction "2_2") (pintype "passive"))
      (node (ref "C4") (pin "2") (pinfunction "2_2") (pintype "passive"))
      (node (ref "C5") (pin "2") (pinfunction "2_2") (pintype "passive"))
      (node (ref "C6") (pin "2") (pinfunction "2_2") (pintype "passive"))
      (node (ref "IC1") (pin "2") (pinfunction "GND_2") (pintype "passive"))
      (node (ref "J10") (pin "1") (pinfunction "1_1") (pintype "passive"))
      (node (ref "J7") (pin "1") (pinfunction "PWR_1") (pintype "passive"))
      (node (ref "Q1") (pin "4") (pintype "passive"))
      (node (ref "R1") (pin "1") (pinfunction "1_1") (pintype "passive"))
      (node (ref "R2") (pin "1") (pinfunction "1_1") (pintype "passive"))
      (node (ref "R4") (pin "1") (pinfunction "1_1") (pintype "passive"))
      (node (ref "R5") (pin "1") (pinfunction "1_1") (pintype "passive"))
      (node (ref "R6") (pin "1") (pinfunction "1_1") (pintype "passive"))
      (node (ref "R7") (pin "1") (pinfunction "1_1") (pintype "passive"))
      (node (ref "U1") (pin "11") (pinfunction "DIAG_11") (pintype "input"))
      (node (ref "U1") (pin "12") (pinfunction "SR_12") (pintype "input"))
      (node (ref "U1") (pin "14") (pinfunction "MODE_14") (pintype "input"))
      (node (ref "U1") (pin "6") (pinfunction "GND_6") (pintype "power_in"))
      (node (ref "U1") (pin "8") (pinfunction "DRVOFF_8") (pintype "input"))
      (node (ref "U4") (pin "11") (pinfunction "DIAG_11") (pintype "input"))
      (node (ref "U4") (pin "12") (pinfunction "SR_12") (pintype "input"))
      (node (ref "U4") (pin "14") (pinfunction "MODE_14") (pintype "input"))
      (node (ref "U4") (pin "6") (pinfunction "GND_6") (pintype "power_in"))
      (node (ref "U4") (pin "8") (pinfunction "DRVOFF_8") (pintype "input"))
      (node (ref "U5") (pin "15") (pinfunction "GND2_15") (pintype "passive"))
      (node (ref "U5") (pin "9") (pinfunction "GND2_9") (pintype "passive"))
      (node (ref "U6") (pin "15") (pinfunction "GND2_15") (pintype "passive"))
      (node (ref "U6") (pin "9") (pinfunction "GND2_9") (pintype "passive"))
      (node (ref "U9") (pin "11") (pinfunction "DIAG_11") (pintype "input"))
      (node (ref "U9") (pin "12") (pinfunction "SR_12") (pintype "input"))
      (node (ref "U9") (pin "14") (pinfunction "MODE_14") (pintype "input"))
      (node (ref "U9") (pin "6") (pinfunction "GND_6") (pintype "power_in"))
      (node (ref "U9") (pin "8") (pinfunction "DRVOFF_8") (pintype "input"))
    )
    (net (code "52") (name "unconnected-(IC1-EN-Pad3)") (class "Default")
      (node (ref "IC1") (pin "3") (pinfunction "EN_3") (pintype "passive"))
    )
    (net (code "53") (name "unconnected-(IC1-NC{slash}ADJ{slash}PG-Pad4)") (class "Default")
      (node (ref "IC1") (pin "4") (pinfunction "NC/ADJ/PG_4") (pintype "passive"))
    )
    (net (code "54") (name "unconnected-(J-ID-Pad4)") (class "Default")
      (node (ref "J") (pin "4") (pinfunction "ID_4") (pintype "passive"))
    )
    (net (code "55") (name "unconnected-(J10-Pad3)") (class "Default")
      (node (ref "J10") (pin "3") (pinfunction "3_3") (pintype "passive"))
    )
    (net (code "56") (name "unconnected-(J10-Pad4)") (class "Default")
      (node (ref "J10") (pin "4") (pinfunction "4_4") (pintype "passive"))
    )
    (net (code "57") (name "unconnected-(P1-Pad6)") (class "Default")
      (node (ref "P1") (pin "6") (pinfunction "6_6") (pintype "passive"))
    )
    (net (code "58") (name "unconnected-(P1-Pad7)") (class "Default")
      (node (ref "P1") (pin "7") (pinfunction "7_7") (pintype "passive"))
    )
    (net (code "59") (name "unconnected-(P1-Pad8)") (class "Default")
      (node (ref "P1") (pin "8") (pinfunction "8_8") (pintype "passive"))
    )
    (net (code "60") (name "unconnected-(U1-~{FAULT}-Pad1)") (class "Default")
      (node (ref "U1") (pin "1") (pinfunction "~{FAULT}_1") (pintype "output"))
    )
    (net (code "61") (name "unconnected-(U2C-PA5-Pad10)") (class "Default")
      (node (ref "U2") (pin "10") (pinfunction "PA5_10") (pintype "passive"))
    )
    (net (code "62") (name "unconnected-(U2C-PA10-Pad20)") (class "Default")
      (node (ref "U2") (pin "20") (pinfunction "PA10_20") (pintype "passive"))
    )
    (net (code "63") (name "unconnected-(U2C-PB0-Pad13)") (class "Default")
      (node (ref "U2") (pin "13") (pinfunction "PB0_13") (pintype "passive"))
    )
    (net (code "64") (name "unconnected-(U2C-PB3-Pad26)") (class "Default")
      (node (ref "U2") (pin "26") (pinfunction "PB3_26") (pintype "passive"))
    )
    (net (code "65") (name "unconnected-(U2C-PB4-Pad27)") (class "Default")
      (node (ref "U2") (pin "27") (pinfunction "PB4_27") (pintype "passive"))
    )
    (net (code "66") (name "unconnected-(U2C-PF1-Pad3)") (class "Default")
      (node (ref "U2") (pin "3") (pinfunction "PF1_3") (pintype "passive"))
    )
    (net (code "67") (name "unconnected-(U4-~{FAULT}-Pad1)") (class "Default")
      (node (ref "U4") (pin "1") (pinfunction "~{FAULT}_1") (pintype "output"))
    )
    (net (code "68") (name "unconnected-(U5-ENB-Pad10)") (class "Default")
      (node (ref "U5") (pin "10") (pinfunction "ENB_10") (pintype "passive"))
    )
    (net (code "69") (name "unconnected-(U5-NC-Pad7)") (class "Default")
      (node (ref "U5") (pin "7") (pinfunction "NC_7") (pintype "passive"))
    )
    (net (code "70") (name "unconnected-(U6-ENB-Pad10)") (class "Default")
      (node (ref "U6") (pin "10") (pinfunction "ENB_10") (pintype "passive"))
    )
    (net (code "71") (name "unconnected-(U6-NC-Pad7)") (class "Default")
      (node (ref "U6") (pin "7") (pinfunction "NC_7") (pintype "passive"))
    )
    (net (code "72") (name "unconnected-(U8-NC-Pad1)") (class "Default")
      (node (ref "U8") (pin "1") (pinfunction "NC_1") (pintype "passive"))
    )
    (net (code "73") (name "unconnected-(U9-~{FAULT}-Pad1)") (class "Default")
      (node (ref "U9") (pin "1") (pinfunction "~{FAULT}_1") (pintype "output"))
    )
  )
)
